# AmplificadorNMOS.net
KiCad netlist of a schematic drawn in Altium Designer
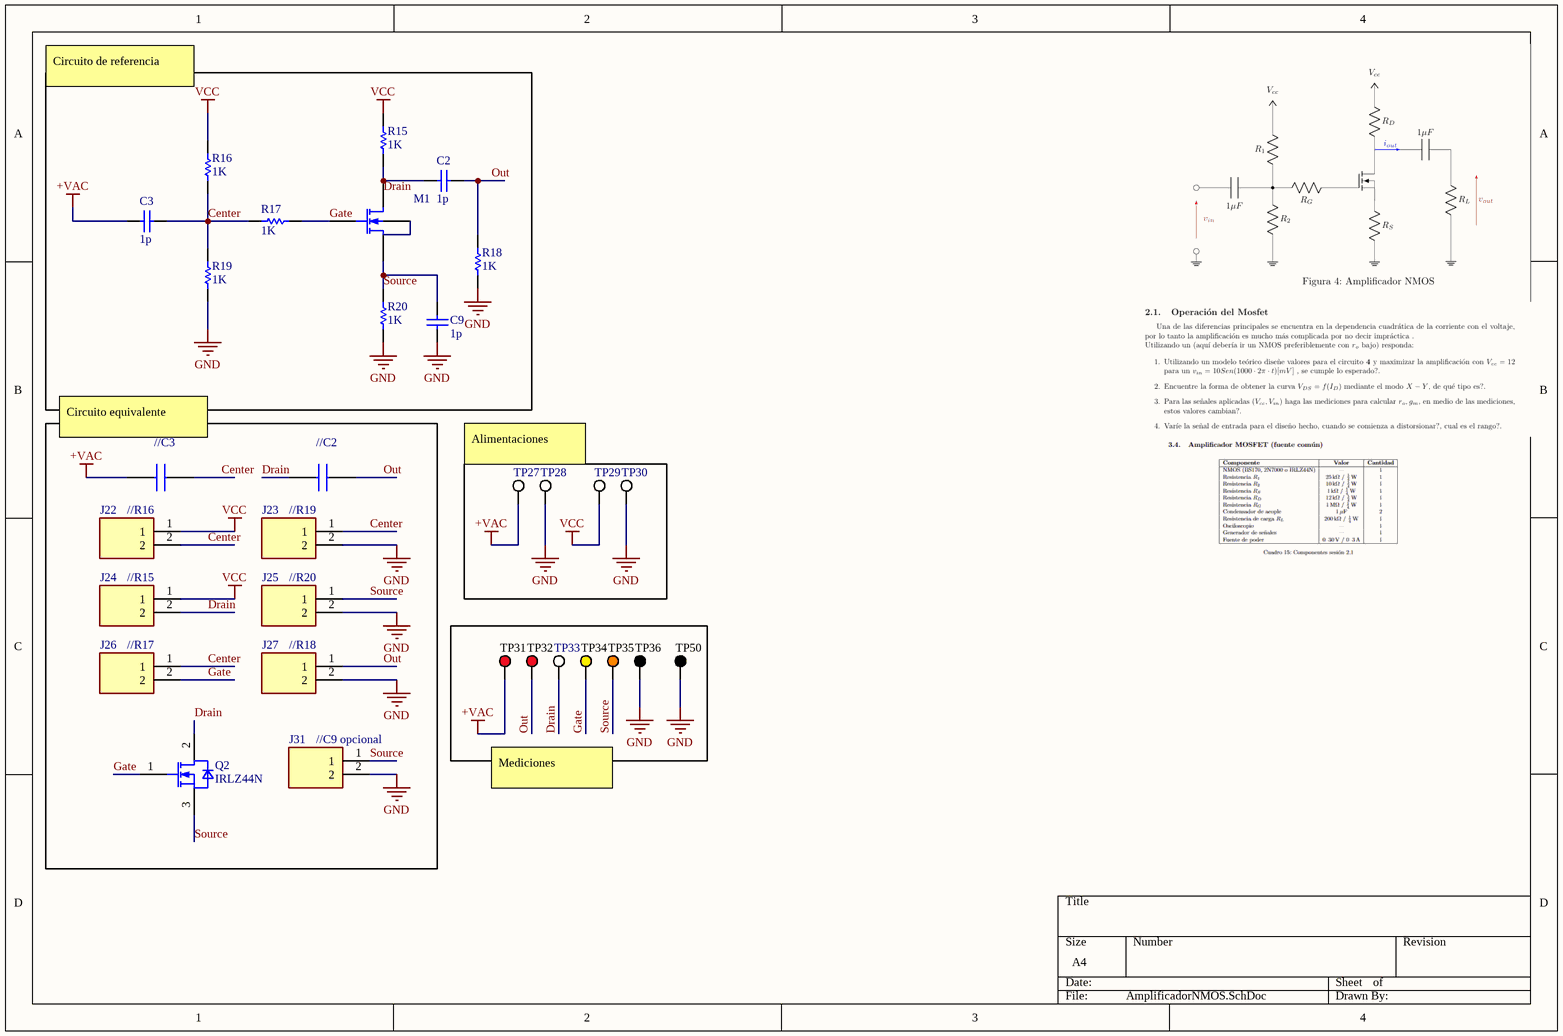
[diagram p0: AmplificadorNMOS.SchDoc]

(export (version "E")
  (design (tool "Eeschema 10.0.6"))
  (components
    (comp (ref "C2")
      (value "1p")
      (description "Capacitor")
      (libsource (lib "Simulation Generic Components") (part "Capacitor"))
    )
    (comp (ref "C3")
      (value "1p")
      (description "Capacitor")
      (libsource (lib "Simulation Generic Components") (part "Capacitor"))
    )
    (comp (ref "C4")
      (value "C1206C105K3RAC7800")
      (footprint "CAPC3216X140N")
      (description "Multilayer Ceramic Capacitors MLCC - SMD/SMT 25V 1uF X7R 1206 10%")
      (fields (field (name "MOUSER PART NUMBER") "80-C1206C105K3R7800"))
      (libsource (lib "Cap1uF") (part "C1206C105K3RAC7800"))
    )
    (comp (ref "C5")
      (value "C1206C105K3RAC7800")
      (footprint "CAPC3216X140N")
      (description "Multilayer Ceramic Capacitors MLCC - SMD/SMT 25V 1uF X7R 1206 10%")
      (fields (field (name "MOUSER PART NUMBER") "80-C1206C105K3R7800"))
      (libsource (lib "Cap1uF") (part "C1206C105K3RAC7800"))
    )
    (comp (ref "C9")
      (value "1p")
      (description "Capacitor")
      (libsource (lib "Simulation Generic Components") (part "Capacitor"))
    )
    (comp (ref "J22")
      (value "D01-9970242")
      (footprint "D019970242")
      (description "IC Socket: 2 Pos Receptacle SIL Straight THT Strip")
      (fields (field (name "MOUSER PART NUMBER") "855-D01-9970242"))
      (libsource (lib "Zocalo_2pines") (part "D01-9970242"))
    )
    (comp (ref "J23")
      (value "D01-9970242")
      (footprint "D019970242")
      (description "IC Socket: 2 Pos Receptacle SIL Straight THT Strip")
      (fields (field (name "MOUSER PART NUMBER") "855-D01-9970242"))
      (libsource (lib "Zocalo_2pines") (part "D01-9970242"))
    )
    (comp (ref "J24")
      (value "D01-9970242")
      (footprint "D019970242")
      (description "IC Socket: 2 Pos Receptacle SIL Straight THT Strip")
      (fields (field (name "MOUSER PART NUMBER") "855-D01-9970242"))
      (libsource (lib "Zocalo_2pines") (part "D01-9970242"))
    )
    (comp (ref "J25")
      (value "D01-9970242")
      (footprint "D019970242")
      (description "IC Socket: 2 Pos Receptacle SIL Straight THT Strip")
      (fields (field (name "MOUSER PART NUMBER") "855-D01-9970242"))
      (libsource (lib "Zocalo_2pines") (part "D01-9970242"))
    )
    (comp (ref "J26")
      (value "D01-9970242")
      (footprint "D019970242")
      (description "IC Socket: 2 Pos Receptacle SIL Straight THT Strip")
      (fields (field (name "MOUSER PART NUMBER") "855-D01-9970242"))
      (libsource (lib "Zocalo_2pines") (part "D01-9970242"))
    )
    (comp (ref "J27")
      (value "D01-9970242")
      (footprint "D019970242")
      (description "IC Socket: 2 Pos Receptacle SIL Straight THT Strip")
      (fields (field (name "MOUSER PART NUMBER") "855-D01-9970242"))
      (libsource (lib "Zocalo_2pines") (part "D01-9970242"))
    )
    (comp (ref "J31")
      (value "D01-9970242")
      (footprint "D019970242")
      (description "IC Socket: 2 Pos Receptacle SIL Straight THT Strip")
      (fields (field (name "MOUSER PART NUMBER") "855-D01-9970242"))
      (libsource (lib "Zocalo_2pines") (part "D01-9970242"))
    )
    (comp (ref "M1")
      (value "N-channel MOS1 MOSFET Shichman and Hodges Model")
      (libsource (lib "Simulation Generic Components") (part "MOSFET N-ch Lev1"))
    )
    (comp (ref "Q2")
      (value "IRLZ44N")
      (footprint "IFX-PG-TO220-3-904-1")
      (description "OptiMOS 3 Power-Transistor, VDS 100V")
      (fields (field (name "MANUFACTURER") "Infineon Technologies"))
      (libsource (lib "IRLZ44N") (part "IRLZ44N"))
    )
    (comp (ref "R15")
      (value "1K")
      (description "Resistor")
      (libsource (lib "Simulation Generic Components") (part "Resistor"))
    )
    (comp (ref "R16")
      (value "1K")
      (description "Resistor")
      (libsource (lib "Simulation Generic Components") (part "Resistor"))
    )
    (comp (ref "R17")
      (value "1K")
      (description "Resistor")
      (libsource (lib "Simulation Generic Components") (part "Resistor"))
    )
    (comp (ref "R18")
      (value "1K")
      (description "Resistor")
      (libsource (lib "Simulation Generic Components") (part "Resistor"))
    )
    (comp (ref "R19")
      (value "1K")
      (description "Resistor")
      (libsource (lib "Simulation Generic Components") (part "Resistor"))
    )
    (comp (ref "R20")
      (value "1K")
      (description "Resistor")
      (libsource (lib "Simulation Generic Components") (part "Resistor"))
    )
    (comp (ref "TP27")
      (value "575-4")
      (footprint "KSTN-575-4")
      (description "Banana Jack, Non-Insulated, 1-Pin THD, RoHS, Bulk")
      (fields (field (name "MANUFACTURER") "Keystone-Electronics"))
      (libsource (lib "Altium Content Vault") (part "TESTPOINT_WHITE"))
    )
    (comp (ref "TP28")
      (value "575-4")
      (footprint "KSTN-575-4")
      (description "Banana Jack, Non-Insulated, 1-Pin THD, RoHS, Bulk")
      (fields (field (name "MANUFACTURER") "Keystone-Electronics"))
      (libsource (lib "Altium Content Vault") (part "TESTPOINT_WHITE"))
    )
    (comp (ref "TP29")
      (value "575-4")
      (footprint "KSTN-575-4")
      (description "Banana Jack, Non-Insulated, 1-Pin THD, RoHS, Bulk")
      (fields (field (name "MANUFACTURER") "Keystone-Electronics"))
      (libsource (lib "Altium Content Vault") (part "TESTPOINT_WHITE"))
    )
    (comp (ref "TP30")
      (value "575-4")
      (footprint "KSTN-575-4")
      (description "Banana Jack, Non-Insulated, 1-Pin THD, RoHS, Bulk")
      (fields (field (name "MANUFACTURER") "Keystone-Electronics"))
      (libsource (lib "Altium Content Vault") (part "TESTPOINT_WHITE"))
    )
    (comp (ref "TP31")
      (value "5010")
      (footprint "KSTN-5010_V")
      (description "Test Point, Red, Through Hole, RoHS, Bulk")
      (fields (field (name "MANUFACTURER") "Keystone"))
      (libsource (lib "Altium Content Vault") (part "TESTPOINT_RED"))
    )
    (comp (ref "TP32")
      (value "5010")
      (footprint "KSTN-5010_V")
      (description "Test Point, Red, Through Hole, RoHS, Bulk")
      (fields (field (name "MANUFACTURER") "Keystone"))
      (libsource (lib "Altium Content Vault") (part "TESTPOINT_RED"))
    )
    (comp (ref "TP33")
      (value "5012")
      (footprint "KSTN-5012_V")
      (description "Test Point, White, Through Hole, RoHS, Bulk")
      (fields (field (name "MANUFACTURER") "Keystone"))
      (libsource (lib "Altium Content Vault") (part "TESTPOINT_WHITE"))
    )
    (comp (ref "TP34")
      (value "5014")
      (footprint "KSTN-5014_V")
      (description "Test Point, Yellow, Through Hole, RoHS, Bulk")
      (fields (field (name "MANUFACTURER") "Keystone"))
      (libsource (lib "Altium Content Vault") (part "TESTPOINT_YELLOW"))
    )
    (comp (ref "TP35")
      (value "5013")
      (footprint "KSTN-5013_V")
      (description "Test Point, Orange, Through Hole, RoHS, Bulk")
      (fields (field (name "MANUFACTURER") "Keystone"))
      (libsource (lib "Altium Content Vault") (part "TESTPOINT_ORANGE"))
    )
    (comp (ref "TP36")
      (value "5011")
      (footprint "KSTN-5011_V")
      (description "Test Point, Black, Through Hole, RoHS, Bulk")
      (fields (field (name "MANUFACTURER") "Keystone"))
      (libsource (lib "Altium Content Vault") (part "TESTPOINT_BLACK"))
    )
    (comp (ref "TP50")
      (value "5011")
      (footprint "KSTN-5011_V")
      (description "Test Point, Black, Through Hole, RoHS, Bulk")
      (fields (field (name "MANUFACTURER") "Keystone"))
      (libsource (lib "Altium Content Vault") (part "TESTPOINT_BLACK"))
    )
  )
  (nets
    (net (code "1") (name "+VAC") (class "Default")
      (node (ref "C3") (pin "1") (pinfunction "1_1") (pintype "passive"))
      (node (ref "C4") (pin "1") (pinfunction "1_1") (pintype "passive"))
      (node (ref "TP27") (pin "1") (pinfunction "1_1") (pintype "passive"))
      (node (ref "TP31") (pin "1") (pinfunction "1_1") (pintype "passive"))
    )
    (net (code "2") (name "/Center") (class "Default")
      (node (ref "C3") (pin "2") (pinfunction "2_2") (pintype "passive"))
      (node (ref "C4") (pin "2") (pinfunction "2_2") (pintype "passive"))
      (node (ref "J22") (pin "2") (pinfunction "2_2") (pintype "passive"))
      (node (ref "J23") (pin "1") (pinfunction "1_1") (pintype "passive"))
      (node (ref "J26") (pin "1") (pinfunction "1_1") (pintype "passive"))
      (node (ref "R16") (pin "2") (pinfunction "2_2") (pintype "passive"))
      (node (ref "R17") (pin "1") (pinfunction "1_1") (pintype "passive"))
      (node (ref "R19") (pin "1") (pinfunction "1_1") (pintype "passive"))
    )
    (net (code "3") (name "/Drain") (class "Default")
      (node (ref "C5") (pin "1") (pinfunction "1_1") (pintype "passive"))
      (node (ref "J24") (pin "2") (pinfunction "2_2") (pintype "passive"))
      (node (ref "Q2") (pin "2") (pinfunction "DRAIN_2") (pintype "passive"))
      (node (ref "TP33") (pin "1") (pinfunction "1_1") (pintype "passive"))
    )
    (net (code "4") (name "/Gate") (class "Default")
      (node (ref "J26") (pin "2") (pinfunction "2_2") (pintype "passive"))
      (node (ref "M1") (pin "2") (pinfunction "G_2") (pintype "passive"))
      (node (ref "Q2") (pin "1") (pinfunction "GATE_1") (pintype "passive"))
      (node (ref "R17") (pin "2") (pinfunction "2_2") (pintype "passive"))
      (node (ref "TP34") (pin "1") (pinfunction "1_1") (pintype "passive"))
    )
    (net (code "5") (name "/Out") (class "Default")
      (node (ref "C2") (pin "2") (pinfunction "2_2") (pintype "passive"))
      (node (ref "C5") (pin "2") (pinfunction "2_2") (pintype "passive"))
      (node (ref "J27") (pin "1") (pinfunction "1_1") (pintype "passive"))
      (node (ref "R18") (pin "2") (pinfunction "2_2") (pintype "passive"))
      (node (ref "TP32") (pin "1") (pinfunction "1_1") (pintype "passive"))
    )
    (net (code "6") (name "/Source") (class "Default")
      (node (ref "C9") (pin "1") (pinfunction "1_1") (pintype "passive"))
      (node (ref "J25") (pin "1") (pinfunction "1_1") (pintype "passive"))
      (node (ref "J31") (pin "1") (pinfunction "1_1") (pintype "passive"))
      (node (ref "M1") (pin "3") (pinfunction "S_3") (pintype "passive"))
      (node (ref "Q2") (pin "3") (pinfunction "SOURCE_3") (pintype "passive"))
      (node (ref "R20") (pin "1") (pinfunction "1_1") (pintype "passive"))
      (node (ref "TP35") (pin "1") (pinfunction "1_1") (pintype "passive"))
    )
    (net (code "7") (name "GND") (class "Default")
      (node (ref "C9") (pin "2") (pinfunction "2_2") (pintype "passive"))
      (node (ref "J23") (pin "2") (pinfunction "2_2") (pintype "passive"))
      (node (ref "J25") (pin "2") (pinfunction "2_2") (pintype "passive"))
      (node (ref "J27") (pin "2") (pinfunction "2_2") (pintype "passive"))
      (node (ref "J31") (pin "2") (pinfunction "2_2") (pintype "passive"))
      (node (ref "R18") (pin "1") (pinfunction "1_1") (pintype "passive"))
      (node (ref "R19") (pin "2") (pinfunction "2_2") (pintype "passive"))
      (node (ref "R20") (pin "2") (pinfunction "2_2") (pintype "passive"))
      (node (ref "TP28") (pin "1") (pinfunction "1_1") (pintype "passive"))
      (node (ref "TP30") (pin "1") (pinfunction "1_1") (pintype "passive"))
      (node (ref "TP36") (pin "1") (pinfunction "1_1") (pintype "passive"))
      (node (ref "TP50") (pin "1") (pinfunction "1_1") (pintype "passive"))
    )
    (net (code "8") (name "Net-(M1-D)") (class "Default")
      (node (ref "C2") (pin "1") (pinfunction "1_1") (pintype "passive"))
      (node (ref "M1") (pin "1") (pinfunction "D_1") (pintype "passive"))
      (node (ref "R15") (pin "2") (pinfunction "2_2") (pintype "passive"))
    )
    (net (code "9") (name "VCC") (class "Default")
      (node (ref "J22") (pin "1") (pinfunction "1_1") (pintype "passive"))
      (node (ref "J24") (pin "1") (pinfunction "1_1") (pintype "passive"))
      (node (ref "R15") (pin "1") (pinfunction "1_1") (pintype "passive"))
      (node (ref "R16") (pin "1") (pinfunction "1_1") (pintype "passive"))
      (node (ref "TP29") (pin "1") (pinfunction "1_1") (pintype "passive"))
    )
    (net (code "10") (name "unconnected-(M1-B-Pad4)") (class "Default")
      (node (ref "M1") (pin "4") (pinfunction "B_4") (pintype "passive"))
    )
  )
)
